# Light_Control_-_8-16_in_16-32_out.net
KiCad netlist of a schematic drawn in Altium Designer
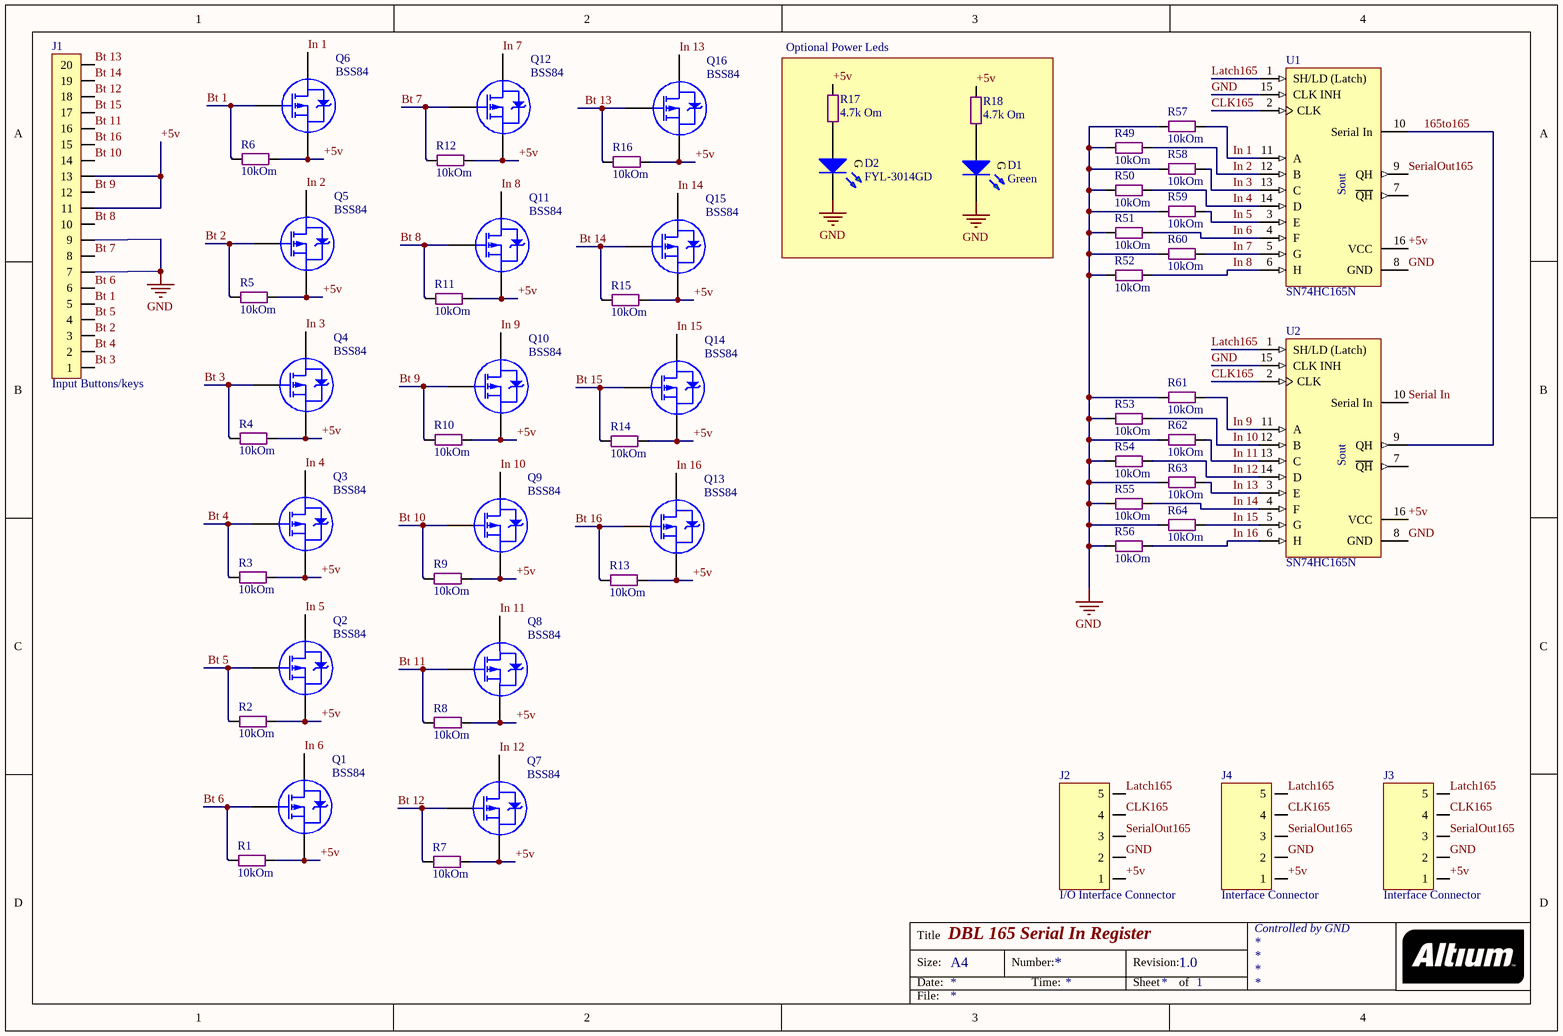
[diagram p0: Light Control - 8-16 in 16-32 out.SchDoc]

(export (version "E")
  (design (tool "Eeschema 10.0.6"))
  (components
    (comp (ref "D1")
      (value "Green")
      (footprint "LED:LED SMD 0805 Green")
      (description "?2v ?20mA")
      (libsource (lib "LED") (part "Led SMD Green"))
    )
    (comp (ref "D2")
      (value "FYL-3014GD")
      (footprint "LED:LED Round 3mm Green")
      (description "2.1v 10mA, 15-30mCd")
      (libsource (lib "LED") (part "Led Round 3mm Green"))
    )
    (comp (ref "J1")
      (value "Input Buttons/keys")
      (footprint "Connector:LINE 2.54 x 20D (2 x 10) - BH")
      (description "Vert, Dbl line, Male")
      (libsource (lib "Connector") (part "PLD-20 (2 x 10)"))
    )
    (comp (ref "J2")
      (value "I/O Interface Connector")
      (footprint "Connector:Line 2.54 x 5")
      (description "Vert, Sgl line, Male")
      (libsource (lib "Connector") (part "PLS-5"))
    )
    (comp (ref "J3")
      (value "Interface Connector")
      (footprint "Connector:Line 2.54 x 5")
      (description "Vert, Sgl line, Male")
      (libsource (lib "Connector") (part "PLS-5"))
    )
    (comp (ref "J4")
      (value "Interface Connector")
      (footprint "Connector:Line 2.54 x 5")
      (description "Vert, Sgl line, Male")
      (libsource (lib "Connector") (part "PLS-5"))
    )
    (comp (ref "Q1")
      (value "BSS84")
      (footprint "GeneralCases:SOT-23")
      (description "P-Channel -50V - 10-1Ω - 0.13A")
      (libsource (lib "Transistor") (part "BSS84"))
    )
    (comp (ref "Q2")
      (value "BSS84")
      (footprint "GeneralCases:SOT-23")
      (description "P-Channel -50V - 10-1Ω - 0.13A")
      (libsource (lib "Transistor") (part "BSS84"))
    )
    (comp (ref "Q3")
      (value "BSS84")
      (footprint "GeneralCases:SOT-23")
      (description "P-Channel -50V - 10-1Ω - 0.13A")
      (libsource (lib "Transistor") (part "BSS84"))
    )
    (comp (ref "Q4")
      (value "BSS84")
      (footprint "GeneralCases:SOT-23")
      (description "P-Channel -50V - 10-1Ω - 0.13A")
      (libsource (lib "Transistor") (part "BSS84"))
    )
    (comp (ref "Q5")
      (value "BSS84")
      (footprint "GeneralCases:SOT-23")
      (description "P-Channel -50V - 10-1Ω - 0.13A")
      (libsource (lib "Transistor") (part "BSS84"))
    )
    (comp (ref "Q6")
      (value "BSS84")
      (footprint "GeneralCases:SOT-23")
      (description "P-Channel -50V - 10-1Ω - 0.13A")
      (libsource (lib "Transistor") (part "BSS84"))
    )
    (comp (ref "Q7")
      (value "BSS84")
      (footprint "GeneralCases:SOT-23")
      (description "P-Channel -50V - 10-1Ω - 0.13A")
      (libsource (lib "Transistor") (part "BSS84"))
    )
    (comp (ref "Q8")
      (value "BSS84")
      (footprint "GeneralCases:SOT-23")
      (description "P-Channel -50V - 10-1Ω - 0.13A")
      (libsource (lib "Transistor") (part "BSS84"))
    )
    (comp (ref "Q9")
      (value "BSS84")
      (footprint "GeneralCases:SOT-23")
      (description "P-Channel -50V - 10-1Ω - 0.13A")
      (libsource (lib "Transistor") (part "BSS84"))
    )
    (comp (ref "Q10")
      (value "BSS84")
      (footprint "GeneralCases:SOT-23")
      (description "P-Channel -50V - 10-1Ω - 0.13A")
      (libsource (lib "Transistor") (part "BSS84"))
    )
    (comp (ref "Q11")
      (value "BSS84")
      (footprint "GeneralCases:SOT-23")
      (description "P-Channel -50V - 10-1Ω - 0.13A")
      (libsource (lib "Transistor") (part "BSS84"))
    )
    (comp (ref "Q12")
      (value "BSS84")
      (footprint "GeneralCases:SOT-23")
      (description "P-Channel -50V - 10-1Ω - 0.13A")
      (libsource (lib "Transistor") (part "BSS84"))
    )
    (comp (ref "Q13")
      (value "BSS84")
      (footprint "GeneralCases:SOT-23")
      (description "P-Channel -50V - 10-1Ω - 0.13A")
      (libsource (lib "Transistor") (part "BSS84"))
    )
    (comp (ref "Q14")
      (value "BSS84")
      (footprint "GeneralCases:SOT-23")
      (description "P-Channel -50V - 10-1Ω - 0.13A")
      (libsource (lib "Transistor") (part "BSS84"))
    )
    (comp (ref "Q15")
      (value "BSS84")
      (footprint "GeneralCases:SOT-23")
      (description "P-Channel -50V - 10-1Ω - 0.13A")
      (libsource (lib "Transistor") (part "BSS84"))
    )
    (comp (ref "Q16")
      (value "BSS84")
      (footprint "GeneralCases:SOT-23")
      (description "P-Channel -50V - 10-1Ω - 0.13A")
      (libsource (lib "Transistor") (part "BSS84"))
    )
    (comp (ref "R1")
      (value "10kOm")
      (footprint "PassiveComponents:SMD 0805 (2012)")
      (libsource (lib "PassiveComponents") (part "Res All Types"))
    )
    (comp (ref "R2")
      (value "10kOm")
      (footprint "PassiveComponents:SMD 0805 (2012)")
      (libsource (lib "PassiveComponents") (part "Res All Types"))
    )
    (comp (ref "R3")
      (value "10kOm")
      (footprint "PassiveComponents:SMD 0805 (2012)")
      (libsource (lib "PassiveComponents") (part "Res All Types"))
    )
    (comp (ref "R4")
      (value "10kOm")
      (footprint "PassiveComponents:SMD 0805 (2012)")
      (libsource (lib "PassiveComponents") (part "Res All Types"))
    )
    (comp (ref "R5")
      (value "10kOm")
      (footprint "PassiveComponents:SMD 0805 (2012)")
      (libsource (lib "PassiveComponents") (part "Res All Types"))
    )
    (comp (ref "R6")
      (value "10kOm")
      (footprint "PassiveComponents:SMD 0805 (2012)")
      (libsource (lib "PassiveComponents") (part "Res All Types"))
    )
    (comp (ref "R7")
      (value "10kOm")
      (footprint "PassiveComponents:SMD 0805 (2012)")
      (libsource (lib "PassiveComponents") (part "Res All Types"))
    )
    (comp (ref "R8")
      (value "10kOm")
      (footprint "PassiveComponents:SMD 0805 (2012)")
      (libsource (lib "PassiveComponents") (part "Res All Types"))
    )
    (comp (ref "R9")
      (value "10kOm")
      (footprint "PassiveComponents:SMD 0805 (2012)")
      (libsource (lib "PassiveComponents") (part "Res All Types"))
    )
    (comp (ref "R10")
      (value "10kOm")
      (footprint "PassiveComponents:SMD 0805 (2012)")
      (libsource (lib "PassiveComponents") (part "Res All Types"))
    )
    (comp (ref "R11")
      (value "10kOm")
      (footprint "PassiveComponents:SMD 0805 (2012)")
      (libsource (lib "PassiveComponents") (part "Res All Types"))
    )
    (comp (ref "R12")
      (value "10kOm")
      (footprint "PassiveComponents:SMD 0805 (2012)")
      (libsource (lib "PassiveComponents") (part "Res All Types"))
    )
    (comp (ref "R13")
      (value "10kOm")
      (footprint "PassiveComponents:SMD 0805 (2012)")
      (libsource (lib "PassiveComponents") (part "Res All Types"))
    )
    (comp (ref "R14")
      (value "10kOm")
      (footprint "PassiveComponents:SMD 0805 (2012)")
      (libsource (lib "PassiveComponents") (part "Res All Types"))
    )
    (comp (ref "R15")
      (value "10kOm")
      (footprint "PassiveComponents:SMD 0805 (2012)")
      (libsource (lib "PassiveComponents") (part "Res All Types"))
    )
    (comp (ref "R16")
      (value "10kOm")
      (footprint "PassiveComponents:SMD 0805 (2012)")
      (libsource (lib "PassiveComponents") (part "Res All Types"))
    )
    (comp (ref "R17")
      (value "4.7k Om")
      (footprint "PassiveComponents:SMD 0805 (2012)")
      (libsource (lib "PassiveComponents") (part "Res All Types"))
    )
    (comp (ref "R18")
      (value "4.7k Om")
      (footprint "PassiveComponents:SMD 0805 (2012)")
      (libsource (lib "PassiveComponents") (part "Res All Types"))
    )
    (comp (ref "R49")
      (value "10kOm")
      (footprint "PassiveComponents:SMD 0805 (2012)")
      (libsource (lib "PassiveComponents") (part "Res All Types"))
    )
    (comp (ref "R50")
      (value "10kOm")
      (footprint "PassiveComponents:SMD 0805 (2012)")
      (libsource (lib "PassiveComponents") (part "Res All Types"))
    )
    (comp (ref "R51")
      (value "10kOm")
      (footprint "PassiveComponents:SMD 0805 (2012)")
      (libsource (lib "PassiveComponents") (part "Res All Types"))
    )
    (comp (ref "R52")
      (value "10kOm")
      (footprint "PassiveComponents:SMD 0805 (2012)")
      (libsource (lib "PassiveComponents") (part "Res All Types"))
    )
    (comp (ref "R53")
      (value "10kOm")
      (footprint "PassiveComponents:SMD 0805 (2012)")
      (libsource (lib "PassiveComponents") (part "Res All Types"))
    )
    (comp (ref "R54")
      (value "10kOm")
      (footprint "PassiveComponents:SMD 0805 (2012)")
      (libsource (lib "PassiveComponents") (part "Res All Types"))
    )
    (comp (ref "R55")
      (value "10kOm")
      (footprint "PassiveComponents:SMD 0805 (2012)")
      (libsource (lib "PassiveComponents") (part "Res All Types"))
    )
    (comp (ref "R56")
      (value "10kOm")
      (footprint "PassiveComponents:SMD 0805 (2012)")
      (libsource (lib "PassiveComponents") (part "Res All Types"))
    )
    (comp (ref "R57")
      (value "10kOm")
      (footprint "PassiveComponents:SMD 0805 (2012)")
      (libsource (lib "PassiveComponents") (part "Res All Types"))
    )
    (comp (ref "R58")
      (value "10kOm")
      (footprint "PassiveComponents:SMD 0805 (2012)")
      (libsource (lib "PassiveComponents") (part "Res All Types"))
    )
    (comp (ref "R59")
      (value "10kOm")
      (footprint "PassiveComponents:SMD 0805 (2012)")
      (libsource (lib "PassiveComponents") (part "Res All Types"))
    )
    (comp (ref "R60")
      (value "10kOm")
      (footprint "PassiveComponents:SMD 0805 (2012)")
      (libsource (lib "PassiveComponents") (part "Res All Types"))
    )
    (comp (ref "R61")
      (value "10kOm")
      (footprint "PassiveComponents:SMD 0805 (2012)")
      (libsource (lib "PassiveComponents") (part "Res All Types"))
    )
    (comp (ref "R62")
      (value "10kOm")
      (footprint "PassiveComponents:SMD 0805 (2012)")
      (libsource (lib "PassiveComponents") (part "Res All Types"))
    )
    (comp (ref "R63")
      (value "10kOm")
      (footprint "PassiveComponents:SMD 0805 (2012)")
      (libsource (lib "PassiveComponents") (part "Res All Types"))
    )
    (comp (ref "R64")
      (value "10kOm")
      (footprint "PassiveComponents:SMD 0805 (2012)")
      (libsource (lib "PassiveComponents") (part "Res All Types"))
    )
    (comp (ref "U1")
      (value "SN74HC165N")
      (footprint "GeneralCases:DIP-16")
      (description "8-Bit Parallel-Load Shift Register")
      (fields (field (name "PUBLISHER") "Altium Limited"))
      (libsource (lib "Chips") (part "SN74HC165N"))
    )
    (comp (ref "U2")
      (value "SN74HC165N")
      (footprint "GeneralCases:DIP-16")
      (description "8-Bit Parallel-Load Shift Register")
      (fields (field (name "PUBLISHER") "Altium Limited"))
      (libsource (lib "Chips") (part "SN74HC165N"))
    )
  )
  (nets
    (net (code "1") (name "/+5v") (class "Default")
      (node (ref "J1") (pin "11") (pinfunction "11_11") (pintype "passive"))
      (node (ref "J1") (pin "13") (pinfunction "13_13") (pintype "passive"))
      (node (ref "J2") (pin "1") (pinfunction "1_1") (pintype "passive"))
      (node (ref "J3") (pin "1") (pinfunction "1_1") (pintype "passive"))
      (node (ref "J4") (pin "1") (pinfunction "1_1") (pintype "passive"))
      (node (ref "Q1") (pin "3") (pinfunction "S_3") (pintype "passive"))
      (node (ref "Q10") (pin "3") (pinfunction "S_3") (pintype "passive"))
      (node (ref "Q11") (pin "3") (pinfunction "S_3") (pintype "passive"))
      (node (ref "Q12") (pin "3") (pinfunction "S_3") (pintype "passive"))
      (node (ref "Q13") (pin "3") (pinfunction "S_3") (pintype "passive"))
      (node (ref "Q14") (pin "3") (pinfunction "S_3") (pintype "passive"))
      (node (ref "Q15") (pin "3") (pinfunction "S_3") (pintype "passive"))
      (node (ref "Q16") (pin "3") (pinfunction "S_3") (pintype "passive"))
      (node (ref "Q2") (pin "3") (pinfunction "S_3") (pintype "passive"))
      (node (ref "Q3") (pin "3") (pinfunction "S_3") (pintype "passive"))
      (node (ref "Q4") (pin "3") (pinfunction "S_3") (pintype "passive"))
      (node (ref "Q5") (pin "3") (pinfunction "S_3") (pintype "passive"))
      (node (ref "Q6") (pin "3") (pinfunction "S_3") (pintype "passive"))
      (node (ref "Q7") (pin "3") (pinfunction "S_3") (pintype "passive"))
      (node (ref "Q8") (pin "3") (pinfunction "S_3") (pintype "passive"))
      (node (ref "Q9") (pin "3") (pinfunction "S_3") (pintype "passive"))
      (node (ref "R1") (pin "1") (pinfunction "1_1") (pintype "passive"))
      (node (ref "R10") (pin "1") (pinfunction "1_1") (pintype "passive"))
      (node (ref "R11") (pin "1") (pinfunction "1_1") (pintype "passive"))
      (node (ref "R12") (pin "1") (pinfunction "1_1") (pintype "passive"))
      (node (ref "R13") (pin "1") (pinfunction "1_1") (pintype "passive"))
      (node (ref "R14") (pin "1") (pinfunction "1_1") (pintype "passive"))
      (node (ref "R15") (pin "1") (pinfunction "1_1") (pintype "passive"))
      (node (ref "R16") (pin "1") (pinfunction "1_1") (pintype "passive"))
      (node (ref "R17") (pin "1") (pinfunction "1_1") (pintype "passive"))
      (node (ref "R18") (pin "1") (pinfunction "1_1") (pintype "passive"))
      (node (ref "R2") (pin "1") (pinfunction "1_1") (pintype "passive"))
      (node (ref "R3") (pin "1") (pinfunction "1_1") (pintype "passive"))
      (node (ref "R4") (pin "1") (pinfunction "1_1") (pintype "passive"))
      (node (ref "R5") (pin "1") (pinfunction "1_1") (pintype "passive"))
      (node (ref "R6") (pin "1") (pinfunction "1_1") (pintype "passive"))
      (node (ref "R7") (pin "1") (pinfunction "1_1") (pintype "passive"))
      (node (ref "R8") (pin "1") (pinfunction "1_1") (pintype "passive"))
      (node (ref "R9") (pin "1") (pinfunction "1_1") (pintype "passive"))
      (node (ref "U1") (pin "16") (pinfunction "VCC_16") (pintype "power_in"))
      (node (ref "U2") (pin "16") (pinfunction "VCC_16") (pintype "power_in"))
    )
    (net (code "2") (name "/165to165") (class "Default")
      (node (ref "U1") (pin "10") (pinfunction "Serial_In_10") (pintype "passive"))
      (node (ref "U2") (pin "9") (pinfunction "QH_9") (pintype "output"))
    )
    (net (code "3") (name "/Bt 1") (class "Default")
      (node (ref "J1") (pin "5") (pinfunction "5_5") (pintype "passive"))
      (node (ref "Q6") (pin "1") (pinfunction "G_1") (pintype "passive"))
      (node (ref "R6") (pin "2") (pinfunction "2_2") (pintype "passive"))
    )
    (net (code "4") (name "/Bt 2") (class "Default")
      (node (ref "J1") (pin "3") (pinfunction "3_3") (pintype "passive"))
      (node (ref "Q5") (pin "1") (pinfunction "G_1") (pintype "passive"))
      (node (ref "R5") (pin "2") (pinfunction "2_2") (pintype "passive"))
    )
    (net (code "5") (name "/Bt 3") (class "Default")
      (node (ref "J1") (pin "1") (pinfunction "1_1") (pintype "passive"))
      (node (ref "Q4") (pin "1") (pinfunction "G_1") (pintype "passive"))
      (node (ref "R4") (pin "2") (pinfunction "2_2") (pintype "passive"))
    )
    (net (code "6") (name "/Bt 4") (class "Default")
      (node (ref "J1") (pin "2") (pinfunction "2_2") (pintype "passive"))
      (node (ref "Q3") (pin "1") (pinfunction "G_1") (pintype "passive"))
      (node (ref "R3") (pin "2") (pinfunction "2_2") (pintype "passive"))
    )
    (net (code "7") (name "/Bt 5") (class "Default")
      (node (ref "J1") (pin "4") (pinfunction "4_4") (pintype "passive"))
      (node (ref "Q2") (pin "1") (pinfunction "G_1") (pintype "passive"))
      (node (ref "R2") (pin "2") (pinfunction "2_2") (pintype "passive"))
    )
    (net (code "8") (name "/Bt 6") (class "Default")
      (node (ref "J1") (pin "6") (pinfunction "6_6") (pintype "passive"))
      (node (ref "Q1") (pin "1") (pinfunction "G_1") (pintype "passive"))
      (node (ref "R1") (pin "2") (pinfunction "2_2") (pintype "passive"))
    )
    (net (code "9") (name "/Bt 7") (class "Default")
      (node (ref "J1") (pin "8") (pinfunction "8_8") (pintype "passive"))
      (node (ref "Q12") (pin "1") (pinfunction "G_1") (pintype "passive"))
      (node (ref "R12") (pin "2") (pinfunction "2_2") (pintype "passive"))
    )
    (net (code "10") (name "/Bt 8") (class "Default")
      (node (ref "J1") (pin "10") (pinfunction "10_10") (pintype "passive"))
      (node (ref "Q11") (pin "1") (pinfunction "G_1") (pintype "passive"))
      (node (ref "R11") (pin "2") (pinfunction "2_2") (pintype "passive"))
    )
    (net (code "11") (name "/Bt 9") (class "Default")
      (node (ref "J1") (pin "12") (pinfunction "12_12") (pintype "passive"))
      (node (ref "Q10") (pin "1") (pinfunction "G_1") (pintype "passive"))
      (node (ref "R10") (pin "2") (pinfunction "2_2") (pintype "passive"))
    )
    (net (code "12") (name "/Bt 10") (class "Default")
      (node (ref "J1") (pin "14") (pinfunction "14_14") (pintype "passive"))
      (node (ref "Q9") (pin "1") (pinfunction "G_1") (pintype "passive"))
      (node (ref "R9") (pin "2") (pinfunction "2_2") (pintype "passive"))
    )
    (net (code "13") (name "/Bt 11") (class "Default")
      (node (ref "J1") (pin "16") (pinfunction "16_16") (pintype "passive"))
      (node (ref "Q8") (pin "1") (pinfunction "G_1") (pintype "passive"))
      (node (ref "R8") (pin "2") (pinfunction "2_2") (pintype "passive"))
    )
    (net (code "14") (name "/Bt 12") (class "Default")
      (node (ref "J1") (pin "18") (pinfunction "18_18") (pintype "passive"))
      (node (ref "Q7") (pin "1") (pinfunction "G_1") (pintype "passive"))
      (node (ref "R7") (pin "2") (pinfunction "2_2") (pintype "passive"))
    )
    (net (code "15") (name "/Bt 13") (class "Default")
      (node (ref "J1") (pin "20") (pinfunction "20_20") (pintype "passive"))
      (node (ref "Q16") (pin "1") (pinfunction "G_1") (pintype "passive"))
      (node (ref "R16") (pin "2") (pinfunction "2_2") (pintype "passive"))
    )
    (net (code "16") (name "/Bt 14") (class "Default")
      (node (ref "J1") (pin "19") (pinfunction "19_19") (pintype "passive"))
      (node (ref "Q15") (pin "1") (pinfunction "G_1") (pintype "passive"))
      (node (ref "R15") (pin "2") (pinfunction "2_2") (pintype "passive"))
    )
    (net (code "17") (name "/Bt 15") (class "Default")
      (node (ref "J1") (pin "17") (pinfunction "17_17") (pintype "passive"))
      (node (ref "Q14") (pin "1") (pinfunction "G_1") (pintype "passive"))
      (node (ref "R14") (pin "2") (pinfunction "2_2") (pintype "passive"))
    )
    (net (code "18") (name "/Bt 16") (class "Default")
      (node (ref "J1") (pin "15") (pinfunction "15_15") (pintype "passive"))
      (node (ref "Q13") (pin "1") (pinfunction "G_1") (pintype "passive"))
      (node (ref "R13") (pin "2") (pinfunction "2_2") (pintype "passive"))
    )
    (net (code "19") (name "/CLK165") (class "Default")
      (node (ref "J2") (pin "4") (pinfunction "4_4") (pintype "passive"))
      (node (ref "J3") (pin "4") (pinfunction "4_4") (pintype "passive"))
      (node (ref "J4") (pin "4") (pinfunction "4_4") (pintype "passive"))
      (node (ref "U1") (pin "2") (pinfunction "CLK_2") (pintype "input"))
      (node (ref "U2") (pin "2") (pinfunction "CLK_2") (pintype "input"))
    )
    (net (code "20") (name "/In 1") (class "Default")
      (node (ref "Q6") (pin "2") (pinfunction "D_2") (pintype "passive"))
      (node (ref "R57") (pin "2") (pinfunction "2_2") (pintype "passive"))
      (node (ref "U1") (pin "11") (pinfunction "A_11") (pintype "input"))
    )
    (net (code "21") (name "/In 2") (class "Default")
      (node (ref "Q5") (pin "2") (pinfunction "D_2") (pintype "passive"))
      (node (ref "R49") (pin "2") (pinfunction "2_2") (pintype "passive"))
      (node (ref "U1") (pin "12") (pinfunction "B_12") (pintype "input"))
    )
    (net (code "22") (name "/In 3") (class "Default")
      (node (ref "Q4") (pin "2") (pinfunction "D_2") (pintype "passive"))
      (node (ref "R58") (pin "2") (pinfunction "2_2") (pintype "passive"))
      (node (ref "U1") (pin "13") (pinfunction "C_13") (pintype "input"))
    )
    (net (code "23") (name "/In 4") (class "Default")
      (node (ref "Q3") (pin "2") (pinfunction "D_2") (pintype "passive"))
      (node (ref "R50") (pin "2") (pinfunction "2_2") (pintype "passive"))
      (node (ref "U1") (pin "14") (pinfunction "D_14") (pintype "input"))
    )
    (net (code "24") (name "/In 5") (class "Default")
      (node (ref "Q2") (pin "2") (pinfunction "D_2") (pintype "passive"))
      (node (ref "R59") (pin "2") (pinfunction "2_2") (pintype "passive"))
      (node (ref "U1") (pin "3") (pinfunction "E_3") (pintype "input"))
    )
    (net (code "25") (name "/In 6") (class "Default")
      (node (ref "Q1") (pin "2") (pinfunction "D_2") (pintype "passive"))
      (node (ref "R51") (pin "2") (pinfunction "2_2") (pintype "passive"))
      (node (ref "U1") (pin "4") (pinfunction "F_4") (pintype "input"))
    )
    (net (code "26") (name "/In 7") (class "Default")
      (node (ref "Q12") (pin "2") (pinfunction "D_2") (pintype "passive"))
      (node (ref "R60") (pin "2") (pinfunction "2_2") (pintype "passive"))
      (node (ref "U1") (pin "5") (pinfunction "G_5") (pintype "input"))
    )
    (net (code "27") (name "/In 8") (class "Default")
      (node (ref "Q11") (pin "2") (pinfunction "D_2") (pintype "passive"))
      (node (ref "R52") (pin "2") (pinfunction "2_2") (pintype "passive"))
      (node (ref "U1") (pin "6") (pinfunction "H_6") (pintype "input"))
    )
    (net (code "28") (name "/In 9") (class "Default")
      (node (ref "Q10") (pin "2") (pinfunction "D_2") (pintype "passive"))
      (node (ref "R61") (pin "2") (pinfunction "2_2") (pintype "passive"))
      (node (ref "U2") (pin "11") (pinfunction "A_11") (pintype "input"))
    )
    (net (code "29") (name "/In 10") (class "Default")
      (node (ref "Q9") (pin "2") (pinfunction "D_2") (pintype "passive"))
      (node (ref "R53") (pin "2") (pinfunction "2_2") (pintype "passive"))
      (node (ref "U2") (pin "12") (pinfunction "B_12") (pintype "input"))
    )
    (net (code "30") (name "/In 11") (class "Default")
      (node (ref "Q8") (pin "2") (pinfunction "D_2") (pintype "passive"))
      (node (ref "R62") (pin "2") (pinfunction "2_2") (pintype "passive"))
      (node (ref "U2") (pin "13") (pinfunction "C_13") (pintype "input"))
    )
    (net (code "31") (name "/In 12") (class "Default")
      (node (ref "Q7") (pin "2") (pinfunction "D_2") (pintype "passive"))
      (node (ref "R54") (pin "2") (pinfunction "2_2") (pintype "passive"))
      (node (ref "U2") (pin "14") (pinfunction "D_14") (pintype "input"))
    )
    (net (code "32") (name "/In 13") (class "Default")
      (node (ref "Q16") (pin "2") (pinfunction "D_2") (pintype "passive"))
      (node (ref "R63") (pin "2") (pinfunction "2_2") (pintype "passive"))
      (node (ref "U2") (pin "3") (pinfunction "E_3") (pintype "input"))
    )
    (net (code "33") (name "/In 14") (class "Default")
      (node (ref "Q15") (pin "2") (pinfunction "D_2") (pintype "passive"))
      (node (ref "R55") (pin "2") (pinfunction "2_2") (pintype "passive"))
      (node (ref "U2") (pin "4") (pinfunction "F_4") (pintype "input"))
    )
    (net (code "34") (name "/In 15") (class "Default")
      (node (ref "Q14") (pin "2") (pinfunction "D_2") (pintype "passive"))
      (node (ref "R64") (pin "2") (pinfunction "2_2") (pintype "passive"))
      (node (ref "U2") (pin "5") (pinfunction "G_5") (pintype "input"))
    )
    (net (code "35") (name "/In 16") (class "Default")
      (node (ref "Q13") (pin "2") (pinfunction "D_2") (pintype "passive"))
      (node (ref "R56") (pin "2") (pinfunction "2_2") (pintype "passive"))
      (node (ref "U2") (pin "6") (pinfunction "H_6") (pintype "input"))
    )
    (net (code "36") (name "/Latch165") (class "Default")
      (node (ref "J2") (pin "5") (pinfunction "5_5") (pintype "passive"))
      (node (ref "J3") (pin "5") (pinfunction "5_5") (pintype "passive"))
      (node (ref "J4") (pin "5") (pinfunction "5_5") (pintype "passive"))
      (node (ref "U1") (pin "1") (pinfunction "SH/LD_(Latch)_1") (pintype "input"))
      (node (ref "U2") (pin "1") (pinfunction "SH/LD_(Latch)_1") (pintype "input"))
    )
    (net (code "37") (name "/Serial In") (class "Default")
      (node (ref "U2") (pin "10") (pinfunction "Serial_In_10") (pintype "passive"))
    )
    (net (code "38") (name "/SerialOut165") (class "Default")
      (node (ref "J2") (pin "3") (pinfunction "3_3") (pintype "passive"))
      (node (ref "J3") (pin "3") (pinfunction "3_3") (pintype "passive"))
      (node (ref "J4") (pin "3") (pinfunction "3_3") (pintype "passive"))
      (node (ref "U1") (pin "9") (pinfunction "QH_9") (pintype "output"))
    )
    (net (code "39") (name "GND") (class "Default")
      (node (ref "D1") (pin "K") (pinfunction "K_K") (pintype "passive"))
      (node (ref "D2") (pin "K") (pinfunction "K_K") (pintype "passive"))
      (node (ref "J1") (pin "7") (pinfunction "7_7") (pintype "passive"))
      (node (ref "J1") (pin "9") (pinfunction "9_9") (pintype "passive"))
      (node (ref "J2") (pin "2") (pinfunction "2_2") (pintype "passive"))
      (node (ref "J3") (pin "2") (pinfunction "2_2") (pintype "passive"))
      (node (ref "J4") (pin "2") (pinfunction "2_2") (pintype "passive"))
      (node (ref "R49") (pin "1") (pinfunction "1_1") (pintype "passive"))
      (node (ref "R50") (pin "1") (pinfunction "1_1") (pintype "passive"))
      (node (ref "R51") (pin "1") (pinfunction "1_1") (pintype "passive"))
      (node (ref "R52") (pin "1") (pinfunction "1_1") (pintype "passive"))
      (node (ref "R53") (pin "1") (pinfunction "1_1") (pintype "passive"))
      (node (ref "R54") (pin "1") (pinfunction "1_1") (pintype "passive"))
      (node (ref "R55") (pin "1") (pinfunction "1_1") (pintype "passive"))
      (node (ref "R56") (pin "1") (pinfunction "1_1") (pintype "passive"))
      (node (ref "R57") (pin "1") (pinfunction "1_1") (pintype "passive"))
      (node (ref "R58") (pin "1") (pinfunction "1_1") (pintype "passive"))
      (node (ref "R59") (pin "1") (pinfunction "1_1") (pintype "passive"))
      (node (ref "R60") (pin "1") (pinfunction "1_1") (pintype "passive"))
      (node (ref "R61") (pin "1") (pinfunction "1_1") (pintype "passive"))
      (node (ref "R62") (pin "1") (pinfunction "1_1") (pintype "passive"))
      (node (ref "R63") (pin "1") (pinfunction "1_1") (pintype "passive"))
      (node (ref "R64") (pin "1") (pinfunction "1_1") (pintype "passive"))
      (node (ref "U1") (pin "15") (pinfunction "CLK_INH_15") (pintype "input"))
      (node (ref "U1") (pin "8") (pinfunction "GND_8") (pintype "power_in"))
      (node (ref "U2") (pin "15") (pinfunction "CLK_INH_15") (pintype "input"))
      (node (ref "U2") (pin "8") (pinfunction "GND_8") (pintype "power_in"))
    )
    (net (code "40") (name "Net-(D1-PadA)") (class "Default")
      (node (ref "D1") (pin "A") (pinfunction "A_A") (pintype "passive"))
      (node (ref "R18") (pin "2") (pinfunction "2_2") (pintype "passive"))
    )
    (net (code "41") (name "Net-(D2-PadA)") (class "Default")
      (node (ref "D2") (pin "A") (pinfunction "A_A") (pintype "passive"))
      (node (ref "R17") (pin "2") (pinfunction "2_2") (pintype "passive"))
    )
    (net (code "42") (name "unconnected-(U1-~{QH}-Pad7)") (class "Default")
      (node (ref "U1") (pin "7") (pinfunction "~{QH}_7") (pintype "output"))
    )
    (net (code "43") (name "unconnected-(U2-~{QH}-Pad7)") (class "Default")
      (node (ref "U2") (pin "7") (pinfunction "~{QH}_7") (pintype "output"))
    )
  )
)
